# 220VAC_to_48V.net
KiCad netlist of a schematic drawn in Altium Designer
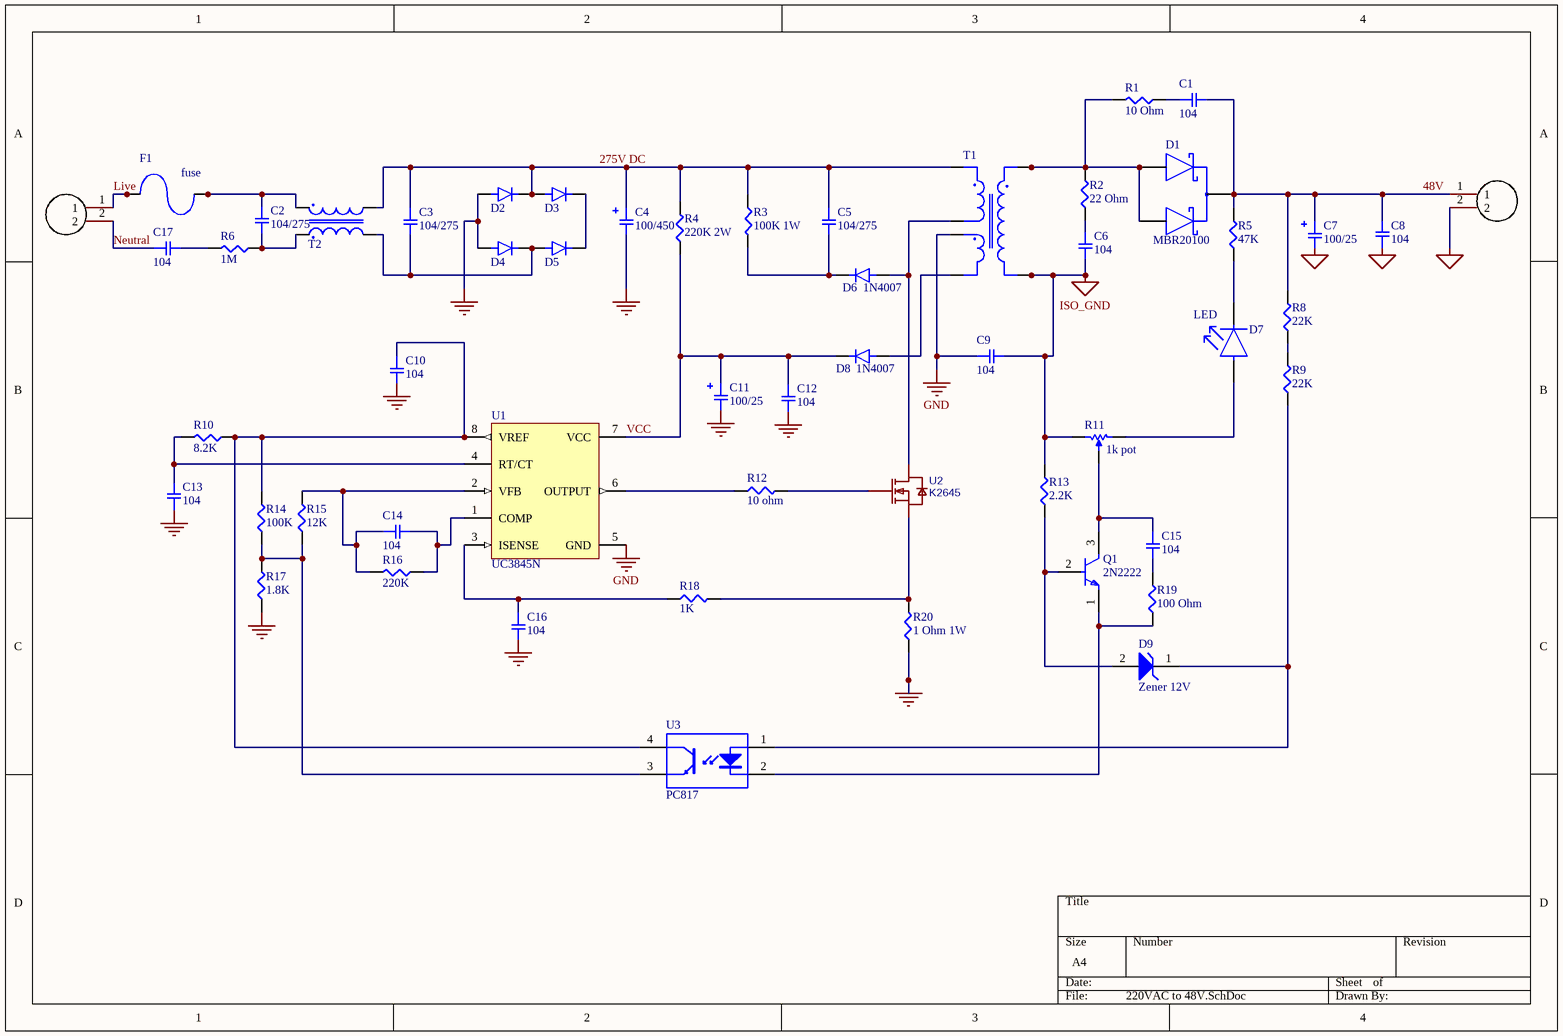
[diagram p0: 220VAC to 48V.SchDoc]

(export (version "E")
  (design (tool "Eeschema 10.0.6"))
  (components
    (comp (ref "C1") (value "104") (footprint "C-1") (libsource (lib "AC220_to_48V") (part "CAPACITOR 104")))
    (comp (ref "C2")
      (value "104/275")
      (footprint "C-15")
      (libsource (lib "AC220_to_48V") (part "CAPACITOR 104/275"))
    )
    (comp (ref "C3")
      (value "104/275")
      (footprint "C-15")
      (libsource (lib "AC220_to_48V") (part "CAPACITOR 104/275"))
    )
    (comp (ref "C4")
      (value "100/450")
      (footprint "C5B2.5")
      (libsource (lib "AC220_to_48V") (part "CAPACITOR 100/450"))
    )
    (comp (ref "C5")
      (value "104/275")
      (footprint "C-15")
      (libsource (lib "AC220_to_48V") (part "CAPACITOR 104/275"))
    )
    (comp (ref "C6") (value "104") (footprint "C-1") (libsource (lib "AC220_to_48V") (part "CAPACITOR 104")))
    (comp (ref "C7")
      (value "100/25")
      (footprint "C2.5-2")
      (libsource (lib "AC220_to_48V") (part "CAPACITOR 100/25"))
    )
    (comp (ref "C8") (value "104") (footprint "C-1") (libsource (lib "AC220_to_48V") (part "CAPACITOR 104")))
    (comp (ref "C9") (value "104") (footprint "C-1") (libsource (lib "AC220_to_48V") (part "CAPACITOR 104")))
    (comp (ref "C10") (value "104") (footprint "C-1") (libsource (lib "AC220_to_48V") (part "CAPACITOR 104")))
    (comp (ref "C11")
      (value "100/25")
      (footprint "C2.5-2")
      (libsource (lib "AC220_to_48V") (part "CAPACITOR 100/25"))
    )
    (comp (ref "C12") (value "104") (footprint "C-1") (libsource (lib "AC220_to_48V") (part "CAPACITOR 104")))
    (comp (ref "C13") (value "104") (footprint "C-1") (libsource (lib "AC220_to_48V") (part "CAPACITOR 104")))
    (comp (ref "C14") (value "104") (footprint "C-1") (libsource (lib "AC220_to_48V") (part "CAPACITOR 104")))
    (comp (ref "C15") (value "104") (footprint "C-1") (libsource (lib "AC220_to_48V") (part "CAPACITOR 104")))
    (comp (ref "C16") (value "104") (footprint "C-1") (libsource (lib "AC220_to_48V") (part "CAPACITOR 104")))
    (comp (ref "C17") (value "104") (footprint "C-1") (libsource (lib "AC220_to_48V") (part "CAPACITOR 104")))
    (comp (ref "CN1")
      (value "WJ2EDGRC-5.08-2P")
      (footprint "Terminal Block P5.08-2P")
      (fields (field (name "MANUFACTURER") "KANGNEX(康奈克斯电气)"))
      (libsource (lib "Terminal Block P5.08-2P") (part "WJ2EDGRC-5.08-2P"))
    )
    (comp (ref "CN2")
      (value "WJ2EDGRC-5.08-2P")
      (footprint "Terminal Block P5.08-2P")
      (fields (field (name "MANUFACTURER") "KANGNEX(康奈克斯电气)"))
      (libsource (lib "Terminal Block P5.08-2P") (part "WJ2EDGRC-5.08-2P"))
    )
    (comp (ref "D1")
      (value "MBR20100")
      (footprint "FP-MBR20100CT-E3-4W-MFG")
      (libsource (lib "MBR20100 schottky diode TH") (part "CMP-00030-42878425-1"))
    )
    (comp (ref "D2")
      (value "1N4007")
      (footprint "FP-1N4007-MFG")
      (description "DIODE GEN PURP 1KV 1A DO204AL")
      (fields
        (field (name "OCTOPART") "https://octopart.com/1n4007-e3%2F54-vishay-39548207")
        (field (name "MANUFACTURER") "Vishay")
      )
      (libsource (lib "1N4007") (part "CMP-02540-000046-1"))
    )
    (comp (ref "D3")
      (value "1N4007")
      (footprint "FP-1N4007-MFG")
      (description "DIODE GEN PURP 1KV 1A DO204AL")
      (fields
        (field (name "OCTOPART") "https://octopart.com/1n4007-e3%2F54-vishay-39548207")
        (field (name "MANUFACTURER") "Vishay")
      )
      (libsource (lib "1N4007") (part "CMP-02540-000046-1"))
    )
    (comp (ref "D4")
      (value "1N4007")
      (footprint "FP-1N4007-MFG")
      (description "DIODE GEN PURP 1KV 1A DO204AL")
      (fields
        (field (name "OCTOPART") "https://octopart.com/1n4007-e3%2F54-vishay-39548207")
        (field (name "MANUFACTURER") "Vishay")
      )
      (libsource (lib "1N4007") (part "CMP-02540-000046-1"))
    )
    (comp (ref "D5")
      (value "1N4007")
      (footprint "FP-1N4007-MFG")
      (description "DIODE GEN PURP 1KV 1A DO204AL")
      (fields
        (field (name "OCTOPART") "https://octopart.com/1n4007-e3%2F54-vishay-39548207")
        (field (name "MANUFACTURER") "Vishay")
      )
      (libsource (lib "1N4007") (part "CMP-02540-000046-1"))
    )
    (comp (ref "D6")
      (value "1N4007")
      (footprint "FP-1N4007-MFG")
      (description "DIODE GEN PURP 1KV 1A DO204AL")
      (fields
        (field (name "OCTOPART") "https://octopart.com/1n4007-e3%2F54-vishay-39548207")
        (field (name "MANUFACTURER") "Vishay")
      )
      (libsource (lib "1N4007") (part "CMP-02540-000046-1"))
    )
    (comp (ref "D7")
      (value "LED")
      (footprint "FP-HLMP-1719-MFG")
      (description "IR LED SFH480")
      (fields
        (field (name "MANUFACTURER") "Broadcom")
        (field (name "OCTOPART") "https://octopart.com/hlmp-1719-broadcom-71130405")
      )
      (libsource (lib "IR LED SFH480") (part "CMP-2000-06410-2"))
    )
    (comp (ref "D8")
      (value "1N4007")
      (footprint "FP-1N4007-MFG")
      (description "DIODE GEN PURP 1KV 1A DO204AL")
      (fields
        (field (name "OCTOPART") "https://octopart.com/1n4007-e3%2F54-vishay-39548207")
        (field (name "MANUFACTURER") "Vishay")
      )
      (libsource (lib "1N4007") (part "CMP-02540-000046-1"))
    )
    (comp (ref "D9")
      (value "Zener 12V")
      (footprint "ONSC-SURMETIC40-2-017AA-01")
      (description "Diode, Zener, Vr 12V, If 200mA, Pkg DO-41, Vf 1.2V, Tj +175C, Cs 380mA, Pd 1.3W, Ir 21mA")
      (fields (field (name "MANUFACTURER") "Vishay") (field (name "MANUFACTURER PART NUMBER") "1N4742A-TR"))
      (libsource (lib "1N4742 Zener 12V TH") (part "1N4742A-TR"))
    )
    (comp (ref "F1") (value "fuse") (footprint "SHK20L") (libsource (lib "AC220_to_48V") (part "fuse")))
    (comp (ref "Q1")
      (value "2N2222")
      (footprint "FP-JAN2N2222A-MFG")
      (description "TRANS NPN 50V 0.8A TO218")
      (libsource (lib "2N2222") (part "CMP-06366-000013-1"))
    )
    (comp (ref "R1")
      (value "10 Ohm")
      (footprint "R7-5")
      (libsource (lib "AC220_to_48V") (part "RESISTOR 1/4W"))
    )
    (comp (ref "R2")
      (value "22 Ohm")
      (footprint "R7-5")
      (libsource (lib "AC220_to_48V") (part "RESISTOR 1/4W"))
    )
    (comp (ref "R3")
      (value "100K 1W")
      (footprint "R-12,5")
      (libsource (lib "AC220_to_48V") (part "RESISTOR 2W"))
    )
    (comp (ref "R4")
      (value "220K 2W")
      (footprint "R-12,5")
      (libsource (lib "AC220_to_48V") (part "RESISTOR 2W"))
    )
    (comp (ref "R5") (value "47K") (footprint "R7-5") (libsource (lib "AC220_to_48V") (part "RESISTOR 1/4W")))
    (comp (ref "R6") (value "1M") (footprint "R7-5") (libsource (lib "AC220_to_48V") (part "RESISTOR 1/4W")))
    (comp (ref "R8") (value "22K") (footprint "R7-5") (libsource (lib "AC220_to_48V") (part "RESISTOR 1/4W")))
    (comp (ref "R9") (value "22K") (footprint "R7-5") (libsource (lib "AC220_to_48V") (part "RESISTOR 1/4W")))
    (comp (ref "R10")
      (value "8.2K")
      (footprint "R7-5")
      (libsource (lib "AC220_to_48V") (part "RESISTOR 1/4W"))
    )
    (comp (ref "R11")
      (value "1k pot")
      (footprint "BOUR-3296W-1-3")
      (description "Square Trimpot(R) Trimming Potentiometer, 1000 Ohm, -55 to 125 degC, 3-Pin THD, RoHS, Tube")
      (fields (field (name "TOLERANCE") "1%"))
      (libsource (lib "1k pot TH") (part "CMP-1747-00002-1"))
    )
    (comp (ref "R12")
      (value "10 ohm")
      (footprint "R7-5")
      (libsource (lib "AC220_to_48V") (part "RESISTOR 1/4W"))
    )
    (comp (ref "R13")
      (value "2.2K")
      (footprint "R7-5")
      (libsource (lib "AC220_to_48V") (part "RESISTOR 1/4W"))
    )
    (comp (ref "R14")
      (value "100K")
      (footprint "R7-5")
      (libsource (lib "AC220_to_48V") (part "RESISTOR 1/4W"))
    )
    (comp (ref "R15")
      (value "12K")
      (footprint "R7-5")
      (libsource (lib "AC220_to_48V") (part "RESISTOR 1/4W"))
    )
    (comp (ref "R16")
      (value "220K")
      (footprint "R7-5")
      (libsource (lib "AC220_to_48V") (part "RESISTOR 1/4W"))
    )
    (comp (ref "R17")
      (value "1.8K")
      (footprint "R7-5")
      (libsource (lib "AC220_to_48V") (part "RESISTOR 1/4W"))
    )
    (comp (ref "R18") (value "1K") (footprint "R7-5") (libsource (lib "AC220_to_48V") (part "RESISTOR 1/4W")))
    (comp (ref "R19")
      (value "100 Ohm")
      (footprint "R7-5")
      (libsource (lib "AC220_to_48V") (part "RESISTOR 1/4W"))
    )
    (comp (ref "R20")
      (value "1 Ohm 1W")
      (footprint "R-12,5")
      (libsource (lib "AC220_to_48V") (part "RESISTOR 2W"))
    )
    (comp (ref "T1")
      (value "Ideal Transformer With Central Tap")
      (footprint "ST-D1")
      (libsource (lib "AC220_to_48V") (part "Transformer With Central Tap Ideal_1"))
    )
    (comp (ref "T2")
      (value "common mode choke")
      (footprint "DFKH14")
      (libsource (lib "AC220_to_48V") (part "Transformer With Central Tap Ideal"))
    )
    (comp (ref "U1")
      (value "UC3845N")
      (footprint "P0008A")
      (fields (field (name "MANUFACTURER") "Texas Instruments"))
      (libsource (lib "UC3845AN") (part "CMP-0319-00305-2"))
    )
    (comp (ref "U2")
      (value "K2645")
      (footprint "TO-220-3_L10.5-W4.8-P2.54-L")
      (fields
        (field (name "MANUFACTURER") "VBsemi(微碧半导体)")
        (field (name "MANUFACTURER PART") "2SK2645-01MR-VB")
        (field (name "CONTRIBUTOR") "lcsc")
      )
      (libsource (lib "2SK2645") (part "2SK2645-01MR-VB"))
    )
    (comp (ref "U3")
      (value "PC817")
      (footprint "LTST-LTV-817-4")
      (fields (field (name "MANUFACTURER") "Lite-On"))
      (libsource (lib "PC817") (part "CMP-2000-06632-1"))
    )
  )
  (nets
    (net (code "1") (name "/48V") (class "Default")
      (node (ref "C1") (pin "2") (pinfunction "2_2") (pintype "passive"))
      (node (ref "C7") (pin "1") (pinfunction "1_1") (pintype "passive"))
      (node (ref "C8") (pin "2") (pinfunction "2_2") (pintype "passive"))
      (node (ref "CN1") (pin "1") (pinfunction "1_1") (pintype "passive"))
      (node (ref "D1") (pin "2") (pinfunction "COMMON_CATHODE_2") (pintype "passive"))
      (node (ref "R5") (pin "2") (pinfunction "2_2") (pintype "passive"))
      (node (ref "R8") (pin "2") (pinfunction "2_2") (pintype "passive"))
    )
    (net (code "2") (name "/275V DC") (class "Default")
      (node (ref "C3") (pin "1") (pinfunction "1_1") (pintype "passive"))
      (node (ref "C4") (pin "1") (pinfunction "1_1") (pintype "passive"))
      (node (ref "C5") (pin "1") (pinfunction "1_1") (pintype "passive"))
      (node (ref "D2") (pin "1") (pinfunction "C_1") (pintype "passive"))
      (node (ref "D3") (pin "2") (pinfunction "A_2") (pintype "passive"))
      (node (ref "R3") (pin "1") (pinfunction "1_1") (pintype "passive"))
      (node (ref "R4") (pin "2") (pinfunction "2_2") (pintype "passive"))
      (node (ref "T1") (pin "7") (pinfunction "7_7") (pintype "passive"))
      (node (ref "T2") (pin "3") (pinfunction "3_3") (pintype "passive"))
    )
    (net (code "3") (name "/Live") (class "Default")
      (node (ref "CN2") (pin "1") (pinfunction "1_1") (pintype "passive"))
      (node (ref "F1") (pin "1A") (pinfunction "1A_1A") (pintype "passive"))
      (node (ref "F1") (pin "1B") (pinfunction "1B_1B") (pintype "passive"))
    )
    (net (code "4") (name "/Neutral") (class "Default")
      (node (ref "C17") (pin "1") (pinfunction "1_1") (pintype "passive"))
      (node (ref "CN2") (pin "2") (pinfunction "2_2") (pintype "passive"))
    )
    (net (code "5") (name "/VCC") (class "Default")
      (node (ref "C11") (pin "1") (pinfunction "1_1") (pintype "passive"))
      (node (ref "C12") (pin "1") (pinfunction "1_1") (pintype "passive"))
      (node (ref "D8") (pin "1") (pinfunction "C_1") (pintype "passive"))
      (node (ref "R4") (pin "1") (pinfunction "1_1") (pintype "passive"))
      (node (ref "U1") (pin "7") (pinfunction "VCC_7") (pintype "power_in"))
    )
    (net (code "6") (name "GND") (class "Default")
      (node (ref "C10") (pin "2") (pinfunction "2_2") (pintype "passive"))
      (node (ref "C11") (pin "2") (pinfunction "2_2") (pintype "passive"))
      (node (ref "C12") (pin "2") (pinfunction "2_2") (pintype "passive"))
      (node (ref "C13") (pin "1") (pinfunction "1_1") (pintype "passive"))
      (node (ref "C16") (pin "2") (pinfunction "2_2") (pintype "passive"))
      (node (ref "C4") (pin "2") (pinfunction "2_2") (pintype "passive"))
      (node (ref "C9") (pin "1") (pinfunction "1_1") (pintype "passive"))
      (node (ref "D2") (pin "2") (pinfunction "A_2") (pintype "passive"))
      (node (ref "D4") (pin "2") (pinfunction "A_2") (pintype "passive"))
      (node (ref "R17") (pin "1") (pinfunction "1_1") (pintype "passive"))
      (node (ref "R20") (pin "1") (pinfunction "1_1") (pintype "passive"))
      (node (ref "T1") (pin "8") (pinfunction "8_8") (pintype "passive"))
      (node (ref "U1") (pin "5") (pinfunction "GND_5") (pintype "power_in"))
    )
    (net (code "7") (name "ISO_GND") (class "Default")
      (node (ref "C6") (pin "2") (pinfunction "2_2") (pintype "passive"))
      (node (ref "C7") (pin "2") (pinfunction "2_2") (pintype "passive"))
      (node (ref "C8") (pin "1") (pinfunction "1_1") (pintype "passive"))
      (node (ref "C9") (pin "2") (pinfunction "2_2") (pintype "passive"))
      (node (ref "CN1") (pin "2") (pinfunction "2_2") (pintype "passive"))
      (node (ref "R11") (pin "3") (pinfunction "B_3") (pintype "passive"))
      (node (ref "R13") (pin "2") (pinfunction "2_2") (pintype "passive"))
      (node (ref "T1") (pin "1") (pinfunction "1_1") (pintype "passive"))
      (node (ref "T1") (pin "2") (pinfunction "2_2") (pintype "passive"))
    )
    (net (code "8") (name "Net-(C1-Pad1)") (class "Default")
      (node (ref "C1") (pin "1") (pinfunction "1_1") (pintype "passive"))
      (node (ref "R1") (pin "1") (pinfunction "1_1") (pintype "passive"))
    )
    (net (code "9") (name "Net-(C2-Pad1)") (class "Default")
      (node (ref "C2") (pin "1") (pinfunction "1_1") (pintype "passive"))
      (node (ref "F1") (pin "2A") (pinfunction "2A_2A") (pintype "passive"))
      (node (ref "F1") (pin "2B") (pinfunction "2B_2B") (pintype "passive"))
      (node (ref "T2") (pin "4") (pinfunction "4_4") (pintype "passive"))
    )
    (net (code "10") (name "Net-(C2-Pad2)") (class "Default")
      (node (ref "C2") (pin "2") (pinfunction "2_2") (pintype "passive"))
      (node (ref "R6") (pin "1") (pinfunction "1_1") (pintype "passive"))
      (node (ref "T2") (pin "1") (pinfunction "1_1") (pintype "passive"))
    )
    (net (code "11") (name "Net-(C6-Pad1)") (class "Default")
      (node (ref "C6") (pin "1") (pinfunction "1_1") (pintype "passive"))
      (node (ref "R2") (pin "1") (pinfunction "1_1") (pintype "passive"))
    )
    (net (code "12") (name "Net-(C15-Pad2)") (class "Default")
      (node (ref "C15") (pin "2") (pinfunction "2_2") (pintype "passive"))
      (node (ref "R19") (pin "2") (pinfunction "2_2") (pintype "passive"))
    )
    (net (code "13") (name "Net-(C17-Pad2)") (class "Default")
      (node (ref "C17") (pin "2") (pinfunction "2_2") (pintype "passive"))
      (node (ref "R6") (pin "2") (pinfunction "2_2") (pintype "passive"))
    )
    (net (code "14") (name "Net-(D1-1_ANODE)") (class "Default")
      (node (ref "D1") (pin "1") (pinfunction "1_ANODE_1") (pintype "passive"))
      (node (ref "D1") (pin "3") (pinfunction "2_ANODE_3") (pintype "passive"))
      (node (ref "R1") (pin "2") (pinfunction "2_2") (pintype "passive"))
      (node (ref "R2") (pin "2") (pinfunction "2_2") (pintype "passive"))
      (node (ref "T1") (pin "5") (pinfunction "5_5") (pintype "passive"))
      (node (ref "T1") (pin "6") (pinfunction "6_6") (pintype "passive"))
    )
    (net (code "15") (name "Net-(D3-C)") (class "Default")
      (node (ref "D3") (pin "1") (pinfunction "C_1") (pintype "passive"))
      (node (ref "D5") (pin "1") (pinfunction "C_1") (pintype "passive"))
    )
    (net (code "16") (name "Net-(D4-C)") (class "Default")
      (node (ref "C3") (pin "2") (pinfunction "2_2") (pintype "passive"))
      (node (ref "D4") (pin "1") (pinfunction "C_1") (pintype "passive"))
      (node (ref "D5") (pin "2") (pinfunction "A_2") (pintype "passive"))
      (node (ref "T2") (pin "2") (pinfunction "2_2") (pintype "passive"))
    )
    (net (code "17") (name "Net-(D6-A)") (class "Default")
      (node (ref "D6") (pin "2") (pinfunction "A_2") (pintype "passive"))
      (node (ref "T1") (pin "9") (pinfunction "9_9") (pintype "passive"))
      (node (ref "U2") (pin "2") (pinfunction "D_2") (pintype "passive"))
    )
    (net (code "18") (name "Net-(D6-C)") (class "Default")
      (node (ref "C5") (pin "2") (pinfunction "2_2") (pintype "passive"))
      (node (ref "D6") (pin "1") (pinfunction "C_1") (pintype "passive"))
      (node (ref "R3") (pin "2") (pinfunction "2_2") (pintype "passive"))
    )
    (net (code "19") (name "Net-(D7-A)") (class "Default")
      (node (ref "D7") (pin "2") (pinfunction "A_2") (pintype "passive"))
      (node (ref "R11") (pin "1") (pinfunction "A_1") (pintype "passive"))
    )
    (net (code "20") (name "Net-(D7-C)") (class "Default")
      (node (ref "D7") (pin "1") (pinfunction "C_1") (pintype "passive"))
      (node (ref "R5") (pin "1") (pinfunction "1_1") (pintype "passive"))
    )
    (net (code "21") (name "Net-(D8-A)") (class "Default")
      (node (ref "D8") (pin "2") (pinfunction "A_2") (pintype "passive"))
      (node (ref "T1") (pin "12") (pinfunction "12_12") (pintype "passive"))
    )
    (net (code "22") (name "Net-(D9-A)") (class "Default")
      (node (ref "D9") (pin "2") (pinfunction "A_2") (pintype "passive"))
      (node (ref "Q1") (pin "2") (pinfunction "B_2") (pintype "passive"))
      (node (ref "R13") (pin "1") (pinfunction "1_1") (pintype "passive"))
    )
    (net (code "23") (name "Net-(D9-K)") (class "Default")
      (node (ref "D9") (pin "1") (pinfunction "K_1") (pintype "passive"))
      (node (ref "R9") (pin "1") (pinfunction "1_1") (pintype "passive"))
      (node (ref "U3") (pin "1") (pinfunction "ANODE_1") (pintype "passive"))
    )
    (net (code "24") (name "Net-(Q1-C)") (class "Default")
      (node (ref "C15") (pin "1") (pinfunction "1_1") (pintype "passive"))
      (node (ref "Q1") (pin "3") (pinfunction "C_3") (pintype "passive"))
      (node (ref "R11") (pin "2") (pinfunction "TAP_2") (pintype "passive"))
    )
    (net (code "25") (name "Net-(Q1-E)") (class "Default")
      (node (ref "Q1") (pin "1") (pinfunction "E_1") (pintype "passive"))
      (node (ref "R19") (pin "1") (pinfunction "1_1") (pintype "passive"))
      (node (ref "U3") (pin "2") (pinfunction "CATHODE_2") (pintype "passive"))
    )
    (net (code "26") (name "Net-(R8-Pad1)") (class "Default")
      (node (ref "R8") (pin "1") (pinfunction "1_1") (pintype "passive"))
      (node (ref "R9") (pin "2") (pinfunction "2_2") (pintype "passive"))
    )
    (net (code "27") (name "Net-(U1-COMP)") (class "Default")
      (node (ref "C14") (pin "2") (pinfunction "2_2") (pintype "passive"))
      (node (ref "R16") (pin "1") (pinfunction "1_1") (pintype "passive"))
      (node (ref "U1") (pin "1") (pinfunction "COMP_1") (pintype "passive"))
    )
    (net (code "28") (name "Net-(U1-ISENSE)") (class "Default")
      (node (ref "C16") (pin "1") (pinfunction "1_1") (pintype "passive"))
      (node (ref "R18") (pin "1") (pinfunction "1_1") (pintype "passive"))
      (node (ref "U1") (pin "3") (pinfunction "ISENSE_3") (pintype "input"))
    )
    (net (code "29") (name "Net-(U1-OUTPUT)") (class "Default")
      (node (ref "R12") (pin "1") (pinfunction "1_1") (pintype "passive"))
      (node (ref "U1") (pin "6") (pinfunction "OUTPUT_6") (pintype "output"))
    )
    (net (code "30") (name "Net-(U1-RT{slash}CT)") (class "Default")
      (node (ref "C13") (pin "2") (pinfunction "2_2") (pintype "passive"))
      (node (ref "R10") (pin "2") (pinfunction "2_2") (pintype "passive"))
      (node (ref "U1") (pin "4") (pinfunction "RT/CT_4") (pintype "passive"))
    )
    (net (code "31") (name "Net-(U1-VFB)") (class "Default")
      (node (ref "C14") (pin "1") (pinfunction "1_1") (pintype "passive"))
      (node (ref "R15") (pin "2") (pinfunction "2_2") (pintype "passive"))
      (node (ref "R16") (pin "2") (pinfunction "2_2") (pintype "passive"))
      (node (ref "U1") (pin "2") (pinfunction "VFB_2") (pintype "input"))
    )
    (net (code "32") (name "Net-(U1-VREF)") (class "Default")
      (node (ref "C10") (pin "1") (pinfunction "1_1") (pintype "passive"))
      (node (ref "R10") (pin "1") (pinfunction "1_1") (pintype "passive"))
      (node (ref "R14") (pin "2") (pinfunction "2_2") (pintype "passive"))
      (node (ref "U1") (pin "8") (pinfunction "VREF_8") (pintype "output"))
      (node (ref "U3") (pin "4") (pinfunction "COLLECTOR_4") (pintype "passive"))
    )
    (net (code "33") (name "Net-(U2-G)") (class "Default")
      (node (ref "R12") (pin "2") (pinfunction "2_2") (pintype "passive"))
      (node (ref "U2") (pin "1") (pinfunction "G_1") (pintype "passive"))
    )
    (net (code "34") (name "Net-(U2-S)") (class "Default")
      (node (ref "R18") (pin "2") (pinfunction "2_2") (pintype "passive"))
      (node (ref "R20") (pin "2") (pinfunction "2_2") (pintype "passive"))
      (node (ref "U2") (pin "3") (pinfunction "S_3") (pintype "passive"))
    )
    (net (code "35") (name "Net-(U3-EMITTER)") (class "Default")
      (node (ref "R14") (pin "1") (pinfunction "1_1") (pintype "passive"))
      (node (ref "R15") (pin "1") (pinfunction "1_1") (pintype "passive"))
      (node (ref "R17") (pin "2") (pinfunction "2_2") (pintype "passive"))
      (node (ref "U3") (pin "3") (pinfunction "EMITTER_3") (pintype "passive"))
    )
  )
)
